# 02_H7_IO.net
KiCad netlist of a schematic drawn in Altium Designer
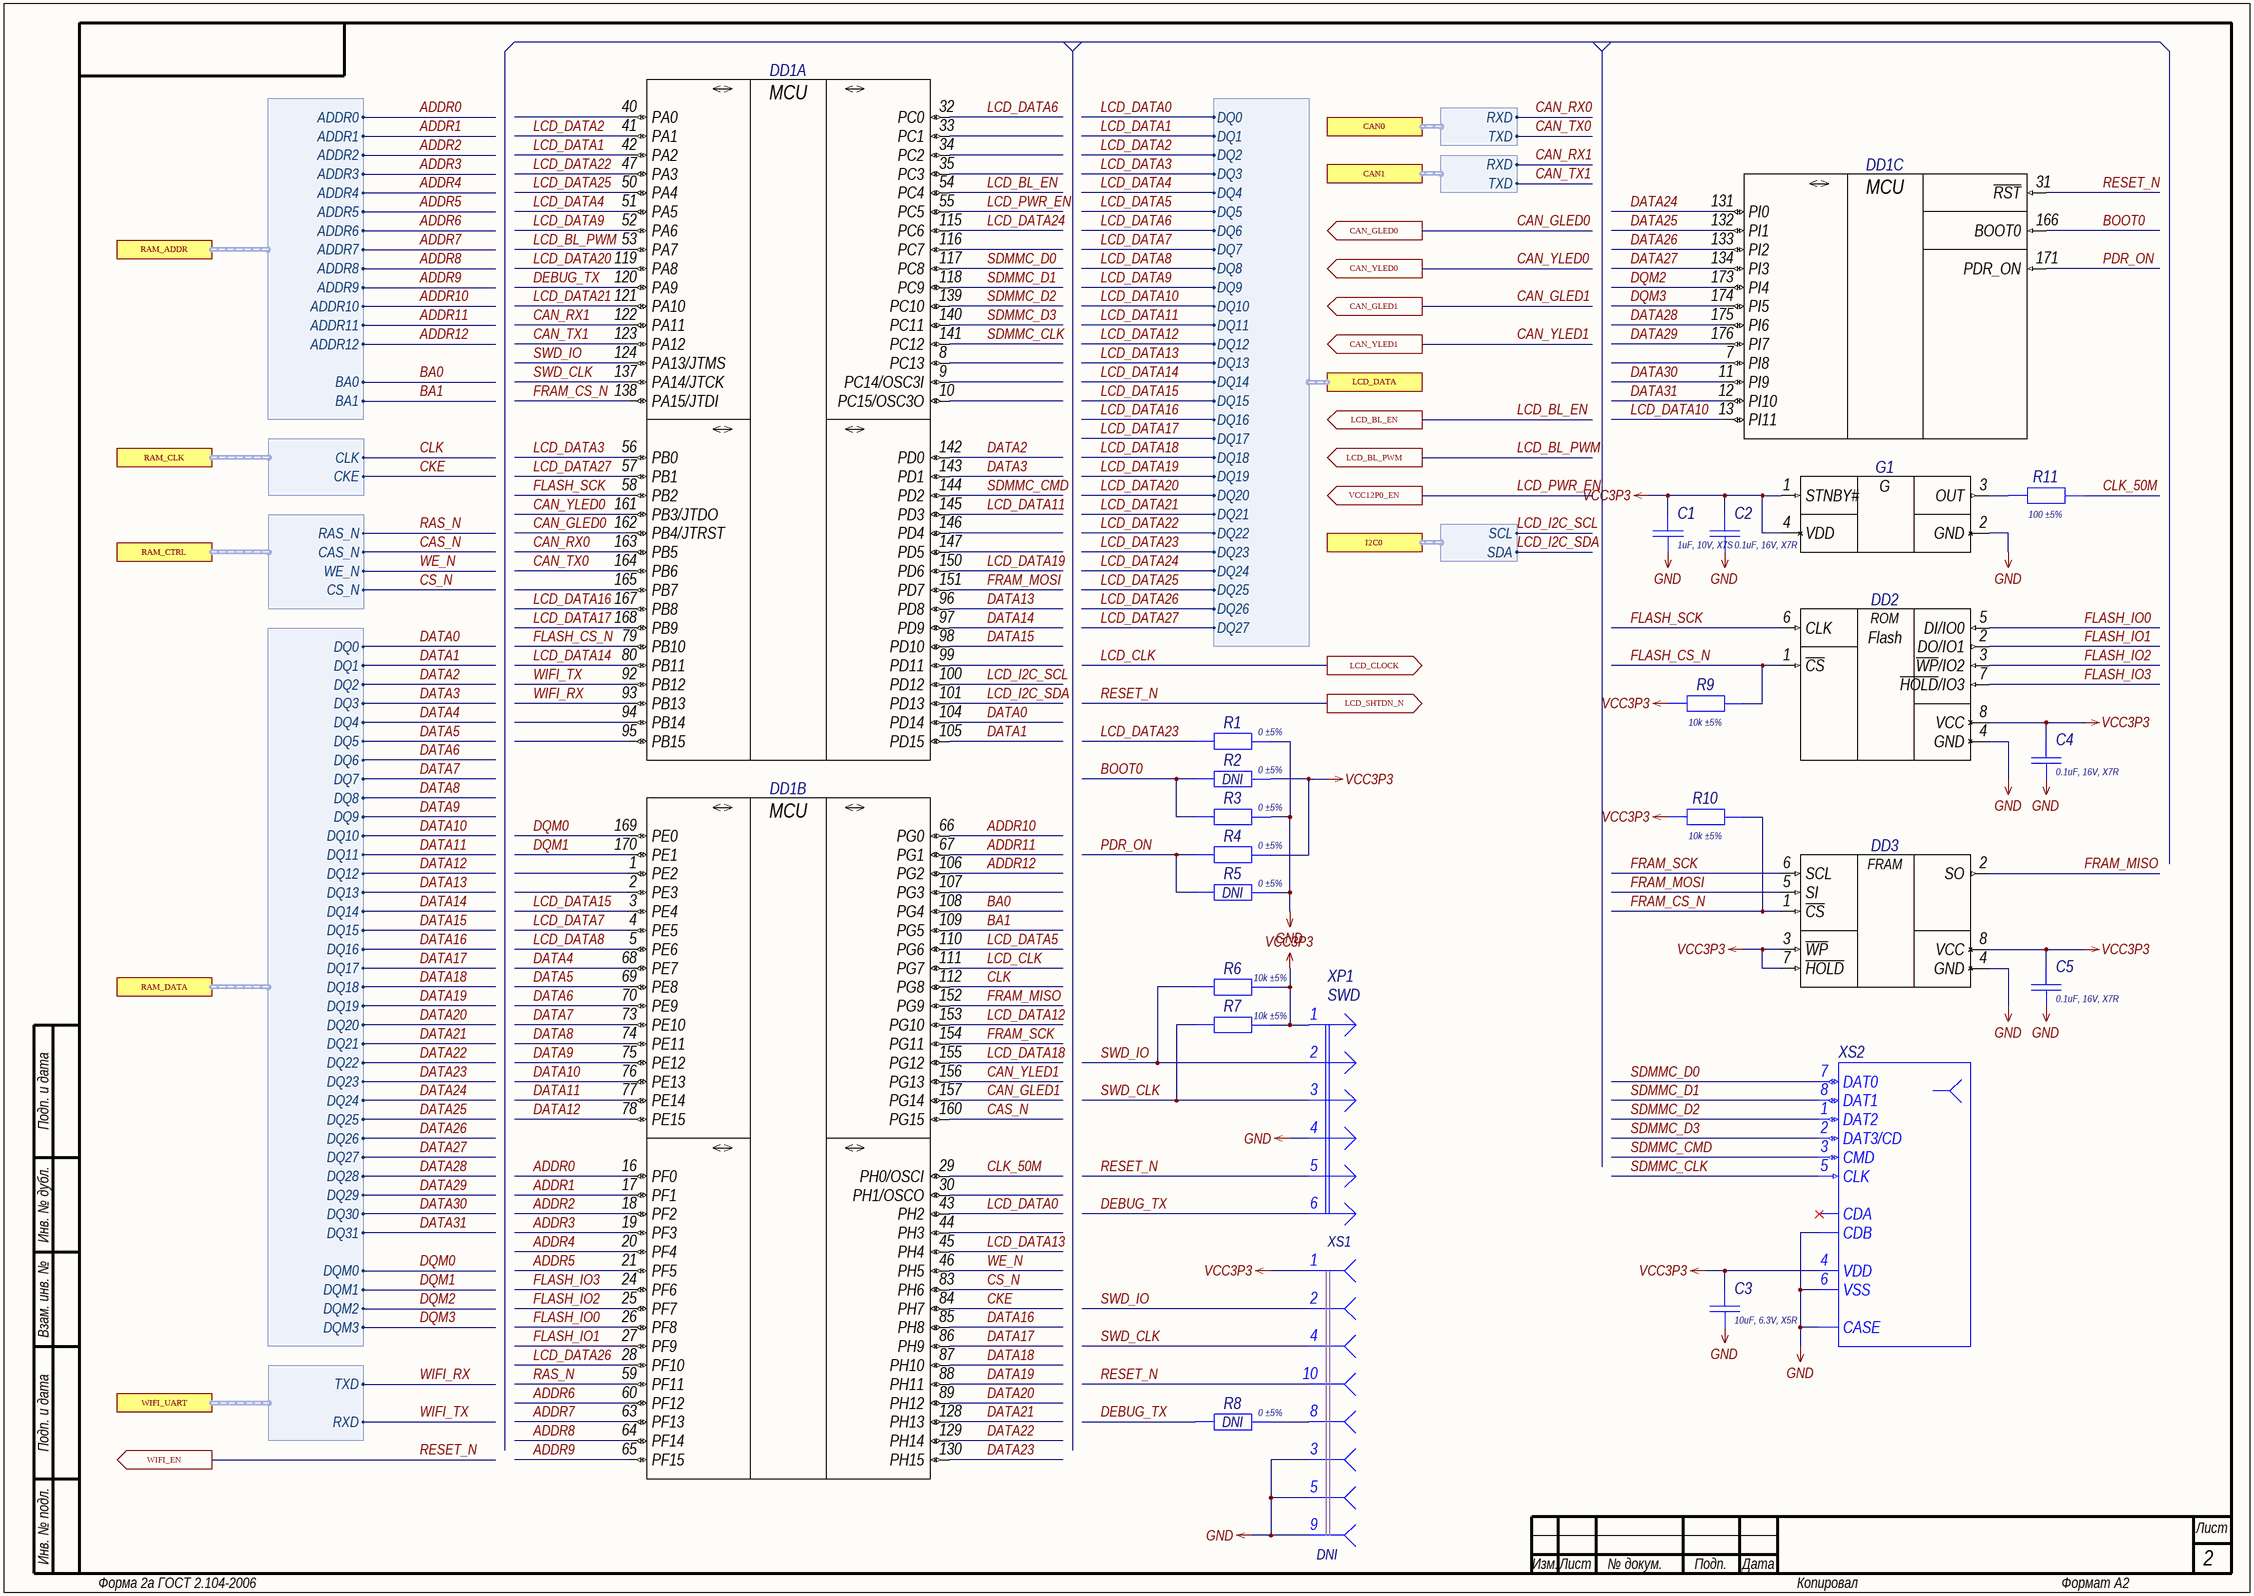
[diagram p0: 02_H7_IO.SchDoc]

(export (version "E")
  (design (tool "Eeschema 10.0.6"))
  (components
    (comp (ref "C1")
      (value "Capacitor")
      (footprint "C0402_L")
      (fields
        (field (name "SCHEMATIC VALUE") "1uF, 10V, X7S")
        (field (name "PART NUMBER") "GRM155C71A105KE11D")
        (field (name "VOLTAGE") "10V")
        (field (name "TOLERANCE") "±10%")
        (field (name "PUBLISHER") "Andrew Danich")
      )
      (libsource (lib "ADLib") (part "Capacitor"))
    )
    (comp (ref "C2")
      (value "Capacitor")
      (footprint "C0402_L")
      (fields
        (field (name "SCHEMATIC VALUE") "0.1uF, 16V, X7R")
        (field (name "PART NUMBER") "GCM155R71C104KA55D")
        (field (name "VOLTAGE") "16V")
        (field (name "TOLERANCE") "±10%")
        (field (name "PUBLISHER") "Andrew Danich")
      )
      (libsource (lib "ADLib") (part "Capacitor"))
    )
    (comp (ref "C3")
      (value "Capacitor")
      (footprint "C0402_L")
      (fields
        (field (name "SCHEMATIC VALUE") "10uF, 6.3V, X5R")
        (field (name "PART NUMBER") "GRM155R60J106ME15D")
        (field (name "VOLTAGE") "6.3V")
        (field (name "TOLERANCE") "±20%")
        (field (name "PUBLISHER") "Andrew Danich")
      )
      (libsource (lib "ADLib") (part "Capacitor"))
    )
    (comp (ref "C4")
      (value "Capacitor")
      (footprint "C0402_L")
      (fields
        (field (name "SCHEMATIC VALUE") "0.1uF, 16V, X7R")
        (field (name "PART NUMBER") "GCM155R71C104KA55D")
        (field (name "VOLTAGE") "16V")
        (field (name "TOLERANCE") "±10%")
        (field (name "PUBLISHER") "Andrew Danich")
      )
      (libsource (lib "ADLib") (part "Capacitor"))
    )
    (comp (ref "C5")
      (value "Capacitor")
      (footprint "C0402_L")
      (fields
        (field (name "SCHEMATIC VALUE") "0.1uF, 16V, X7R")
        (field (name "PART NUMBER") "GCM155R71C104KA55D")
        (field (name "VOLTAGE") "16V")
        (field (name "TOLERANCE") "±10%")
        (field (name "PUBLISHER") "Andrew Danich")
      )
      (libsource (lib "ADLib") (part "Capacitor"))
    )
    (comp (ref "DD1")
      (value "STM32H743IxT6-Series")
      (footprint "LQFP-176_050P2400X2400X160_N")
      (fields
        (field (name "PART NUMBER") "STM32H743IIT6")
        (field (name "MANUFACTURER") "STMicroelectronics")
        (field (name "PUBLISHER") "Andrew Danich")
      )
      (libsource (lib "ADLib") (part "STM32H743IxT6-Series"))
    )
    (comp (ref "DD2")
      (value "W25Q-Series")
      (footprint "SOIC-8_127P528X528X203_N")
      (fields
        (field (name "PART NUMBER") "W25Q128JVSIQ")
        (field (name "MANUFACTURER") "Winbond")
        (field (name "PUBLISHER") "Andrew Danich")
      )
      (libsource (lib "ADLib") (part "W25Q-Series"))
    )
    (comp (ref "DD3")
      (value "FM25CL64Bx-Series")
      (footprint "SOIC-8_127P490X391X155_N")
      (fields
        (field (name "PART NUMBER") "FM25CL64B-G")
        (field (name "MANUFACTURER") "Cypress Semiconductor")
        (field (name "PUBLISHER") "Andrew Danich")
      )
      (libsource (lib "ADLib") (part "FM25CL64Bx-Series"))
    )
    (comp (ref "G1")
      (value "DSC100X-Series")
      (footprint "CDFN-4_165P250X200X085_N")
      (fields
        (field (name "PART NUMBER") "DSC1001DI5-050.0000")
        (field (name "MANUFACTURER") "Microchip")
        (field (name "PUBLISHER") "Andrew Danich")
      )
      (libsource (lib "ADLib") (part "DSC100X-Series"))
    )
    (comp (ref "R1")
      (value "Resistor")
      (footprint "R0402_L")
      (fields
        (field (name "SCHEMATIC VALUE") "0 ±5%")
        (field (name "PART NUMBER") "RC0402JR-070RL")
        (field (name "TOLERANCE") "±5%")
        (field (name "MANUFACTURER") "Yageo")
        (field (name "PUBLISHER") "Andrew Danich")
      )
      (libsource (lib "ADLib") (part "Resistor"))
    )
    (comp (ref "R2")
      (value "Resistor")
      (footprint "R0402_L")
      (fields
        (field (name "SCHEMATIC VALUE") "0 ±5%")
        (field (name "PART NUMBER") "RC0402JR-070RL")
        (field (name "TOLERANCE") "±5%")
        (field (name "MANUFACTURER") "Yageo")
        (field (name "PUBLISHER") "Andrew Danich")
      )
      (libsource (lib "ADLib") (part "Resistor"))
    )
    (comp (ref "R3")
      (value "Resistor")
      (footprint "R0402_L")
      (fields
        (field (name "SCHEMATIC VALUE") "0 ±5%")
        (field (name "PART NUMBER") "RC0402JR-070RL")
        (field (name "TOLERANCE") "±5%")
        (field (name "MANUFACTURER") "Yageo")
        (field (name "PUBLISHER") "Andrew Danich")
      )
      (libsource (lib "ADLib") (part "Resistor"))
    )
    (comp (ref "R4")
      (value "Resistor")
      (footprint "R0402_L")
      (fields
        (field (name "SCHEMATIC VALUE") "0 ±5%")
        (field (name "PART NUMBER") "RC0402JR-070RL")
        (field (name "TOLERANCE") "±5%")
        (field (name "MANUFACTURER") "Yageo")
        (field (name "PUBLISHER") "Andrew Danich")
      )
      (libsource (lib "ADLib") (part "Resistor"))
    )
    (comp (ref "R5")
      (value "Resistor")
      (footprint "R0402_L")
      (fields
        (field (name "SCHEMATIC VALUE") "0 ±5%")
        (field (name "PART NUMBER") "RC0402JR-070RL")
        (field (name "TOLERANCE") "±5%")
        (field (name "MANUFACTURER") "Yageo")
        (field (name "PUBLISHER") "Andrew Danich")
      )
      (libsource (lib "ADLib") (part "Resistor"))
    )
    (comp (ref "R6")
      (value "Resistor")
      (footprint "R0402_L")
      (fields
        (field (name "SCHEMATIC VALUE") "10k ±5%")
        (field (name "PART NUMBER") "RC0402JR-0710KL")
        (field (name "TOLERANCE") "±5%")
        (field (name "MANUFACTURER") "Yageo")
        (field (name "PUBLISHER") "Andrew Danich")
      )
      (libsource (lib "ADLib") (part "Resistor"))
    )
    (comp (ref "R7")
      (value "Resistor")
      (footprint "R0402_L")
      (fields
        (field (name "SCHEMATIC VALUE") "10k ±5%")
        (field (name "PART NUMBER") "RC0402JR-0710KL")
        (field (name "TOLERANCE") "±5%")
        (field (name "MANUFACTURER") "Yageo")
        (field (name "PUBLISHER") "Andrew Danich")
      )
      (libsource (lib "ADLib") (part "Resistor"))
    )
    (comp (ref "R8")
      (value "Resistor")
      (footprint "R0402_L")
      (fields
        (field (name "SCHEMATIC VALUE") "0 ±5%")
        (field (name "PART NUMBER") "RC0402JR-070RL")
        (field (name "TOLERANCE") "±5%")
        (field (name "MANUFACTURER") "Yageo")
        (field (name "PUBLISHER") "Andrew Danich")
      )
      (libsource (lib "ADLib") (part "Resistor"))
    )
    (comp (ref "R9")
      (value "Resistor")
      (footprint "R0402_L")
      (fields
        (field (name "SCHEMATIC VALUE") "10k ±5%")
        (field (name "PART NUMBER") "RC0402JR-0710KL")
        (field (name "TOLERANCE") "±5%")
        (field (name "MANUFACTURER") "Yageo")
        (field (name "PUBLISHER") "Andrew Danich")
      )
      (libsource (lib "ADLib") (part "Resistor"))
    )
    (comp (ref "R10")
      (value "Resistor")
      (footprint "R0402_L")
      (fields
        (field (name "SCHEMATIC VALUE") "10k ±5%")
        (field (name "PART NUMBER") "RC0402JR-0710KL")
        (field (name "TOLERANCE") "±5%")
        (field (name "MANUFACTURER") "Yageo")
        (field (name "PUBLISHER") "Andrew Danich")
      )
      (libsource (lib "ADLib") (part "Resistor"))
    )
    (comp (ref "R11")
      (value "Resistor")
      (footprint "R0402_L")
      (fields
        (field (name "SCHEMATIC VALUE") "100 ±5%")
        (field (name "PART NUMBER") "RC0402JR-07100RL")
        (field (name "TOLERANCE") "±5%")
        (field (name "MANUFACTURER") "Yageo")
        (field (name "PUBLISHER") "Andrew Danich")
      )
      (libsource (lib "ADLib") (part "Resistor"))
    )
    (comp (ref "XP1")
      (value "SWD")
      (footprint "CWF-6R")
      (fields
        (field (name "PART NUMBER") "CWF-6R")
        (field (name "MANUFACTURER") "Ningbo Zhenqin Electronic")
        (field (name "PUBLISHER") "Andrew Danich")
      )
      (libsource (lib "ADLib") (part "Con-6-M"))
    )
    (comp (ref "XS1")
      (value "JTAG")
      (footprint "XF2M-1015-1A")
      (fields
        (field (name "PART NUMBER") "XF2M-1015-1A")
        (field (name "MANUFACTURER") "Omron Electronics")
        (field (name "PUBLISHER") "Viktor Klishin")
      )
      (libsource (lib "ADLib") (part "Con-10-F_S"))
    )
    (comp (ref "XS2")
      (value "DM3AT-SF-PEJM5")
      (footprint "DM3AT-SF-PEJM5")
      (fields (field (name "MANUFACTURER") "Hirose Connector") (field (name "PUBLISHER") "Andrew Danich"))
      (libsource (lib "ADLib") (part "DM3AT-SF-PEJM5"))
    )
  )
  (nets
    (net (code "9") (name "/ADDR0") (class "Default")
      (node (ref "DD1") (pin "16") (pinfunction "PF0_16") (pintype "bidirectional"))
    )
    (net (code "10") (name "/ADDR1") (class "Default")
      (node (ref "DD1") (pin "17") (pinfunction "PF1_17") (pintype "bidirectional"))
    )
    (net (code "11") (name "/ADDR2") (class "Default")
      (node (ref "DD1") (pin "18") (pinfunction "PF2_18") (pintype "bidirectional"))
    )
    (net (code "12") (name "/ADDR3") (class "Default")
      (node (ref "DD1") (pin "19") (pinfunction "PF3_19") (pintype "bidirectional"))
    )
    (net (code "13") (name "/ADDR4") (class "Default")
      (node (ref "DD1") (pin "20") (pinfunction "PF4_20") (pintype "bidirectional"))
    )
    (net (code "14") (name "/ADDR5") (class "Default")
      (node (ref "DD1") (pin "21") (pinfunction "PF5_21") (pintype "bidirectional"))
    )
    (net (code "15") (name "/ADDR6") (class "Default")
      (node (ref "DD1") (pin "60") (pinfunction "PF12_60") (pintype "bidirectional"))
    )
    (net (code "16") (name "/ADDR7") (class "Default")
      (node (ref "DD1") (pin "63") (pinfunction "PF13_63") (pintype "bidirectional"))
    )
    (net (code "17") (name "/ADDR8") (class "Default")
      (node (ref "DD1") (pin "64") (pinfunction "PF14_64") (pintype "bidirectional"))
    )
    (net (code "18") (name "/ADDR9") (class "Default")
      (node (ref "DD1") (pin "65") (pinfunction "PF15_65") (pintype "bidirectional"))
    )
    (net (code "19") (name "/ADDR10") (class "Default")
      (node (ref "DD1") (pin "66") (pinfunction "PG0_66") (pintype "bidirectional"))
    )
    (net (code "20") (name "/ADDR11") (class "Default")
      (node (ref "DD1") (pin "67") (pinfunction "PG1_67") (pintype "bidirectional"))
    )
    (net (code "21") (name "/ADDR12") (class "Default")
      (node (ref "DD1") (pin "106") (pinfunction "PG2_106") (pintype "bidirectional"))
    )
    (net (code "22") (name "/BA0") (class "Default")
      (node (ref "DD1") (pin "108") (pinfunction "PG4_108") (pintype "bidirectional"))
    )
    (net (code "23") (name "/BA1") (class "Default")
      (node (ref "DD1") (pin "109") (pinfunction "PG5_109") (pintype "bidirectional"))
    )
    (net (code "24") (name "/BOOT0") (class "Default")
      (node (ref "DD1") (pin "166") (pinfunction "BOOT0_166") (pintype "input"))
      (node (ref "R2") (pin "1") (pinfunction "1_1") (pintype "passive"))
      (node (ref "R3") (pin "1") (pinfunction "1_1") (pintype "passive"))
    )
    (net (code "25") (name "/CAN_GLED0") (class "Default")
      (node (ref "DD1") (pin "162") (pinfunction "PB4/JTRST_162") (pintype "bidirectional"))
    )
    (net (code "26") (name "/CAN_GLED1") (class "Default")
      (node (ref "DD1") (pin "157") (pinfunction "PG14_157") (pintype "bidirectional"))
    )
    (net (code "27") (name "/CAN_RX0") (class "Default")
      (node (ref "DD1") (pin "163") (pinfunction "PB5_163") (pintype "bidirectional"))
    )
    (net (code "28") (name "/CAN_RX1") (class "Default")
      (node (ref "DD1") (pin "122") (pinfunction "PA11_122") (pintype "bidirectional"))
    )
    (net (code "29") (name "/CAN_TX0") (class "Default")
      (node (ref "DD1") (pin "164") (pinfunction "PB6_164") (pintype "bidirectional"))
    )
    (net (code "30") (name "/CAN_TX1") (class "Default")
      (node (ref "DD1") (pin "123") (pinfunction "PA12_123") (pintype "bidirectional"))
    )
    (net (code "31") (name "/CAN_YLED0") (class "Default")
      (node (ref "DD1") (pin "161") (pinfunction "PB3/JTDO_161") (pintype "bidirectional"))
    )
    (net (code "32") (name "/CAN_YLED1") (class "Default")
      (node (ref "DD1") (pin "156") (pinfunction "PG13_156") (pintype "bidirectional"))
    )
    (net (code "33") (name "/CAS_N") (class "Default")
      (node (ref "DD1") (pin "160") (pinfunction "PG15_160") (pintype "bidirectional"))
    )
    (net (code "34") (name "/CKE") (class "Default")
      (node (ref "DD1") (pin "84") (pinfunction "PH7_84") (pintype "bidirectional"))
    )
    (net (code "35") (name "/CLK") (class "Default")
      (node (ref "DD1") (pin "112") (pinfunction "PG8_112") (pintype "bidirectional"))
    )
    (net (code "36") (name "/CLK_50M") (class "Default")
      (node (ref "DD1") (pin "29") (pinfunction "PH0/OSCI_29") (pintype "bidirectional"))
      (node (ref "R11") (pin "2") (pinfunction "2_2") (pintype "passive"))
    )
    (net (code "37") (name "/CS_N") (class "Default")
      (node (ref "DD1") (pin "83") (pinfunction "PH6_83") (pintype "bidirectional"))
    )
    (net (code "38") (name "/DATA0") (class "Default")
      (node (ref "DD1") (pin "104") (pinfunction "PD14_104") (pintype "bidirectional"))
    )
    (net (code "39") (name "/DATA1") (class "Default")
      (node (ref "DD1") (pin "105") (pinfunction "PD15_105") (pintype "bidirectional"))
    )
    (net (code "40") (name "/DATA2") (class "Default")
      (node (ref "DD1") (pin "142") (pinfunction "PD0_142") (pintype "bidirectional"))
    )
    (net (code "41") (name "/DATA3") (class "Default")
      (node (ref "DD1") (pin "143") (pinfunction "PD1_143") (pintype "bidirectional"))
    )
    (net (code "42") (name "/DATA4") (class "Default")
      (node (ref "DD1") (pin "68") (pinfunction "PE7_68") (pintype "bidirectional"))
    )
    (net (code "43") (name "/DATA5") (class "Default")
      (node (ref "DD1") (pin "69") (pinfunction "PE8_69") (pintype "bidirectional"))
    )
    (net (code "44") (name "/DATA6") (class "Default")
      (node (ref "DD1") (pin "70") (pinfunction "PE9_70") (pintype "bidirectional"))
    )
    (net (code "45") (name "/DATA7") (class "Default")
      (node (ref "DD1") (pin "73") (pinfunction "PE10_73") (pintype "bidirectional"))
    )
    (net (code "46") (name "/DATA8") (class "Default")
      (node (ref "DD1") (pin "74") (pinfunction "PE11_74") (pintype "bidirectional"))
    )
    (net (code "47") (name "/DATA9") (class "Default")
      (node (ref "DD1") (pin "75") (pinfunction "PE12_75") (pintype "bidirectional"))
    )
    (net (code "48") (name "/DATA10") (class "Default")
      (node (ref "DD1") (pin "76") (pinfunction "PE13_76") (pintype "bidirectional"))
    )
    (net (code "49") (name "/DATA11") (class "Default")
      (node (ref "DD1") (pin "77") (pinfunction "PE14_77") (pintype "bidirectional"))
    )
    (net (code "50") (name "/DATA12") (class "Default")
      (node (ref "DD1") (pin "78") (pinfunction "PE15_78") (pintype "bidirectional"))
    )
    (net (code "51") (name "/DATA13") (class "Default")
      (node (ref "DD1") (pin "96") (pinfunction "PD8_96") (pintype "bidirectional"))
    )
    (net (code "52") (name "/DATA14") (class "Default")
      (node (ref "DD1") (pin "97") (pinfunction "PD9_97") (pintype "bidirectional"))
    )
    (net (code "53") (name "/DATA15") (class "Default")
      (node (ref "DD1") (pin "98") (pinfunction "PD10_98") (pintype "bidirectional"))
    )
    (net (code "54") (name "/DATA16") (class "Default")
      (node (ref "DD1") (pin "85") (pinfunction "PH8_85") (pintype "bidirectional"))
    )
    (net (code "55") (name "/DATA17") (class "Default")
      (node (ref "DD1") (pin "86") (pinfunction "PH9_86") (pintype "bidirectional"))
    )
    (net (code "56") (name "/DATA18") (class "Default")
      (node (ref "DD1") (pin "87") (pinfunction "PH10_87") (pintype "bidirectional"))
    )
    (net (code "57") (name "/DATA19") (class "Default")
      (node (ref "DD1") (pin "88") (pinfunction "PH11_88") (pintype "bidirectional"))
    )
    (net (code "58") (name "/DATA20") (class "Default")
      (node (ref "DD1") (pin "89") (pinfunction "PH12_89") (pintype "bidirectional"))
    )
    (net (code "59") (name "/DATA21") (class "Default")
      (node (ref "DD1") (pin "128") (pinfunction "PH13_128") (pintype "bidirectional"))
    )
    (net (code "60") (name "/DATA22") (class "Default")
      (node (ref "DD1") (pin "129") (pinfunction "PH14_129") (pintype "bidirectional"))
    )
    (net (code "61") (name "/DATA23") (class "Default")
      (node (ref "DD1") (pin "130") (pinfunction "PH15_130") (pintype "bidirectional"))
    )
    (net (code "62") (name "/DATA24") (class "Default")
      (node (ref "DD1") (pin "131") (pinfunction "PI0_131") (pintype "bidirectional"))
    )
    (net (code "63") (name "/DATA25") (class "Default")
      (node (ref "DD1") (pin "132") (pinfunction "PI1_132") (pintype "bidirectional"))
    )
    (net (code "64") (name "/DATA26") (class "Default")
      (node (ref "DD1") (pin "133") (pinfunction "PI2_133") (pintype "bidirectional"))
    )
    (net (code "65") (name "/DATA27") (class "Default")
      (node (ref "DD1") (pin "134") (pinfunction "PI3_134") (pintype "bidirectional"))
    )
    (net (code "66") (name "/DATA28") (class "Default")
      (node (ref "DD1") (pin "175") (pinfunction "PI6_175") (pintype "bidirectional"))
    )
    (net (code "67") (name "/DATA29") (class "Default")
      (node (ref "DD1") (pin "176") (pinfunction "PI7_176") (pintype "bidirectional"))
    )
    (net (code "68") (name "/DATA30") (class "Default")
      (node (ref "DD1") (pin "11") (pinfunction "PI9_11") (pintype "bidirectional"))
    )
    (net (code "69") (name "/DATA31") (class "Default")
      (node (ref "DD1") (pin "12") (pinfunction "PI10_12") (pintype "bidirectional"))
    )
    (net (code "70") (name "/DEBUG_TX") (class "Default")
      (node (ref "DD1") (pin "120") (pinfunction "PA9_120") (pintype "bidirectional"))
      (node (ref "R8") (pin "1") (pinfunction "1_1") (pintype "passive"))
      (node (ref "XP1") (pin "6") (pintype "passive"))
    )
    (net (code "71") (name "/DQM0") (class "Default")
      (node (ref "DD1") (pin "169") (pinfunction "PE0_169") (pintype "bidirectional"))
    )
    (net (code "72") (name "/DQM1") (class "Default")
      (node (ref "DD1") (pin "170") (pinfunction "PE1_170") (pintype "bidirectional"))
    )
    (net (code "73") (name "/DQM2") (class "Default")
      (node (ref "DD1") (pin "173") (pinfunction "PI4_173") (pintype "bidirectional"))
    )
    (net (code "74") (name "/DQM3") (class "Default")
      (node (ref "DD1") (pin "174") (pinfunction "PI5_174") (pintype "bidirectional"))
    )
    (net (code "75") (name "/FLASH_CS_N") (class "Default")
      (node (ref "DD1") (pin "79") (pinfunction "PB10_79") (pintype "bidirectional"))
      (node (ref "DD2") (pin "1") (pinfunction "~{CS}_1") (pintype "input"))
      (node (ref "R9") (pin "1") (pinfunction "1_1") (pintype "passive"))
    )
    (net (code "76") (name "/FLASH_IO0") (class "Default")
      (node (ref "DD1") (pin "26") (pinfunction "PF8_26") (pintype "bidirectional"))
      (node (ref "DD2") (pin "5") (pinfunction "DI/IO0_5") (pintype "input"))
    )
    (net (code "77") (name "/FLASH_IO1") (class "Default")
      (node (ref "DD1") (pin "27") (pinfunction "PF9_27") (pintype "bidirectional"))
      (node (ref "DD2") (pin "2") (pinfunction "DO/IO1_2") (pintype "output"))
    )
    (net (code "78") (name "/FLASH_IO2") (class "Default")
      (node (ref "DD1") (pin "25") (pinfunction "PF7_25") (pintype "bidirectional"))
      (node (ref "DD2") (pin "3") (pinfunction "~{WP}/IO2_3") (pintype "input"))
    )
    (net (code "79") (name "/FLASH_IO3") (class "Default")
      (node (ref "DD1") (pin "24") (pinfunction "PF6_24") (pintype "bidirectional"))
      (node (ref "DD2") (pin "7") (pinfunction "~{HOLD}/IO3_7") (pintype "input"))
    )
    (net (code "80") (name "/FLASH_SCK") (class "Default")
      (node (ref "DD1") (pin "58") (pinfunction "PB2_58") (pintype "bidirectional"))
      (node (ref "DD2") (pin "6") (pinfunction "CLK_6") (pintype "input"))
    )
    (net (code "81") (name "/FRAM_CS_N") (class "Default")
      (node (ref "DD1") (pin "138") (pinfunction "PA15/JTDI_138") (pintype "bidirectional"))
      (node (ref "DD3") (pin "1") (pinfunction "~{CS}_1") (pintype "input"))
      (node (ref "R10") (pin "1") (pinfunction "1_1") (pintype "passive"))
    )
    (net (code "82") (name "/FRAM_MISO") (class "Default")
      (node (ref "DD1") (pin "152") (pinfunction "PG9_152") (pintype "bidirectional"))
      (node (ref "DD3") (pin "2") (pinfunction "SO_2") (pintype "output"))
    )
    (net (code "83") (name "/FRAM_MOSI") (class "Default")
      (node (ref "DD1") (pin "151") (pinfunction "PD7_151") (pintype "bidirectional"))
      (node (ref "DD3") (pin "5") (pinfunction "SI_5") (pintype "input"))
    )
    (net (code "84") (name "/FRAM_SCK") (class "Default")
      (node (ref "DD1") (pin "154") (pinfunction "PG11_154") (pintype "bidirectional"))
      (node (ref "DD3") (pin "6") (pinfunction "SCL_6") (pintype "input"))
    )
    (net (code "85") (name "/LCD_BL_EN") (class "Default")
      (node (ref "DD1") (pin "54") (pinfunction "PC4_54") (pintype "bidirectional"))
    )
    (net (code "86") (name "/LCD_BL_PWM") (class "Default")
      (node (ref "DD1") (pin "53") (pinfunction "PA7_53") (pintype "bidirectional"))
    )
    (net (code "87") (name "/LCD_CLK") (class "Default")
      (node (ref "DD1") (pin "111") (pinfunction "PG7_111") (pintype "bidirectional"))
    )
    (net (code "88") (name "/LCD_DATA0") (class "Default")
      (node (ref "DD1") (pin "43") (pinfunction "PH2_43") (pintype "bidirectional"))
    )
    (net (code "89") (name "/LCD_DATA1") (class "Default")
      (node (ref "DD1") (pin "42") (pinfunction "PA2_42") (pintype "bidirectional"))
    )
    (net (code "90") (name "/LCD_DATA2") (class "Default")
      (node (ref "DD1") (pin "41") (pinfunction "PA1_41") (pintype "bidirectional"))
    )
    (net (code "91") (name "/LCD_DATA3") (class "Default")
      (node (ref "DD1") (pin "56") (pinfunction "PB0_56") (pintype "bidirectional"))
    )
    (net (code "92") (name "/LCD_DATA4") (class "Default")
      (node (ref "DD1") (pin "51") (pinfunction "PA5_51") (pintype "bidirectional"))
    )
    (net (code "93") (name "/LCD_DATA5") (class "Default")
      (node (ref "DD1") (pin "110") (pinfunction "PG6_110") (pintype "bidirectional"))
    )
    (net (code "94") (name "/LCD_DATA6") (class "Default")
      (node (ref "DD1") (pin "32") (pinfunction "PC0_32") (pintype "bidirectional"))
    )
    (net (code "95") (name "/LCD_DATA7") (class "Default")
      (node (ref "DD1") (pin "4") (pinfunction "PE5_4") (pintype "bidirectional"))
    )
    (net (code "96") (name "/LCD_DATA8") (class "Default")
      (node (ref "DD1") (pin "5") (pinfunction "PE6_5") (pintype "bidirectional"))
    )
    (net (code "97") (name "/LCD_DATA9") (class "Default")
      (node (ref "DD1") (pin "52") (pinfunction "PA6_52") (pintype "bidirectional"))
    )
    (net (code "98") (name "/LCD_DATA10") (class "Default")
      (node (ref "DD1") (pin "13") (pinfunction "PI11_13") (pintype "bidirectional"))
    )
    (net (code "99") (name "/LCD_DATA11") (class "Default")
      (node (ref "DD1") (pin "145") (pinfunction "PD3_145") (pintype "bidirectional"))
    )
    (net (code "100") (name "/LCD_DATA12") (class "Default")
      (node (ref "DD1") (pin "153") (pinfunction "PG10_153") (pintype "bidirectional"))
    )
    (net (code "101") (name "/LCD_DATA13") (class "Default")
      (node (ref "DD1") (pin "45") (pinfunction "PH4_45") (pintype "bidirectional"))
    )
    (net (code "102") (name "/LCD_DATA14") (class "Default")
      (node (ref "DD1") (pin "80") (pinfunction "PB11_80") (pintype "bidirectional"))
    )
    (net (code "103") (name "/LCD_DATA15") (class "Default")
      (node (ref "DD1") (pin "3") (pinfunction "PE4_3") (pintype "bidirectional"))
    )
    (net (code "104") (name "/LCD_DATA16") (class "Default")
      (node (ref "DD1") (pin "167") (pinfunction "PB8_167") (pintype "bidirectional"))
    )
    (net (code "105") (name "/LCD_DATA17") (class "Default")
      (node (ref "DD1") (pin "168") (pinfunction "PB9_168") (pintype "bidirectional"))
    )
    (net (code "106") (name "/LCD_DATA18") (class "Default")
      (node (ref "DD1") (pin "155") (pinfunction "PG12_155") (pintype "bidirectional"))
    )
    (net (code "107") (name "/LCD_DATA19") (class "Default")
      (node (ref "DD1") (pin "150") (pinfunction "PD6_150") (pintype "bidirectional"))
    )
    (net (code "108") (name "/LCD_DATA20") (class "Default")
      (node (ref "DD1") (pin "119") (pinfunction "PA8_119") (pintype "bidirectional"))
    )
    (net (code "109") (name "/LCD_DATA21") (class "Default")
      (node (ref "DD1") (pin "121") (pinfunction "PA10_121") (pintype "bidirectional"))
    )
    (net (code "110") (name "/LCD_DATA22") (class "Default")
      (node (ref "DD1") (pin "47") (pinfunction "PA3_47") (pintype "bidirectional"))
    )
    (net (code "111") (name "/LCD_DATA23") (class "Default")
      (node (ref "R1") (pin "1") (pinfunction "1_1") (pintype "passive"))
    )
    (net (code "112") (name "/LCD_DATA24") (class "Default")
      (node (ref "DD1") (pin "115") (pinfunction "PC6_115") (pintype "bidirectional"))
    )
    (net (code "113") (name "/LCD_DATA25") (class "Default")
      (node (ref "DD1") (pin "50") (pinfunction "PA4_50") (pintype "bidirectional"))
    )
    (net (code "114") (name "/LCD_DATA26") (class "Default")
      (node (ref "DD1") (pin "28") (pinfunction "PF10_28") (pintype "bidirectional"))
    )
    (net (code "115") (name "/LCD_DATA27") (class "Default")
      (node (ref "DD1") (pin "57") (pinfunction "PB1_57") (pintype "bidirectional"))
    )
    (net (code "116") (name "/LCD_I2C_SCL") (class "Default")
      (node (ref "DD1") (pin "100") (pinfunction "PD12_100") (pintype "bidirectional"))
    )
    (net (code "117") (name "/LCD_I2C_SDA") (class "Default")
      (node (ref "DD1") (pin "101") (pinfunction "PD13_101") (pintype "bidirectional"))
    )
    (net (code "118") (name "/LCD_PWR_EN") (class "Default")
      (node (ref "DD1") (pin "55") (pinfunction "PC5_55") (pintype "bidirectional"))
    )
    (net (code "119") (name "/PDR_ON") (class "Default")
      (node (ref "DD1") (pin "171") (pinfunction "PDR_ON_171") (pintype "input"))
      (node (ref "R4") (pin "1") (pinfunction "1_1") (pintype "passive"))
      (node (ref "R5") (pin "1") (pinfunction "1_1") (pintype "passive"))
    )
    (net (code "120") (name "/RAS_N") (class "Default")
      (node (ref "DD1") (pin "59") (pinfunction "PF11_59") (pintype "bidirectional"))
    )
    (net (code "121") (name "/RESET_N") (class "Default")
      (node (ref "DD1") (pin "31") (pinfunction "~{RST}_31") (pintype "input"))
      (node (ref "XP1") (pin "5") (pintype "passive"))
      (node (ref "XS1") (pin "10") (pintype "passive"))
    )
    (net (code "122") (name "/SDMMC_CLK") (class "Default")
      (node (ref "DD1") (pin "141") (pinfunction "PC12_141") (pintype "bidirectional"))
      (node (ref "XS2") (pin "5") (pinfunction "CLK_5") (pintype "input"))
    )
    (net (code "123") (name "/SDMMC_CMD") (class "Default")
      (node (ref "DD1") (pin "144") (pinfunction "PD2_144") (pintype "bidirectional"))
      (node (ref "XS2") (pin "3") (pinfunction "CMD_3") (pintype "bidirectional"))
    )
    (net (code "124") (name "/SDMMC_D0") (class "Default")
      (node (ref "DD1") (pin "117") (pinfunction "PC8_117") (pintype "bidirectional"))
      (node (ref "XS2") (pin "7") (pinfunction "DAT0_7") (pintype "bidirectional"))
    )
    (net (code "125") (name "/SDMMC_D1") (class "Default")
      (node (ref "DD1") (pin "118") (pinfunction "PC9_118") (pintype "bidirectional"))
      (node (ref "XS2") (pin "8") (pinfunction "DAT1_8") (pintype "bidirectional"))
    )
    (net (code "126") (name "/SDMMC_D2") (class "Default")
      (node (ref "DD1") (pin "139") (pinfunction "PC10_139") (pintype "bidirectional"))
      (node (ref "XS2") (pin "1") (pinfunction "DAT2_1") (pintype "bidirectional"))
    )
    (net (code "127") (name "/SDMMC_D3") (class "Default")
      (node (ref "DD1") (pin "140") (pinfunction "PC11_140") (pintype "bidirectional"))
      (node (ref "XS2") (pin "2") (pinfunction "DAT3/CD_2") (pintype "bidirectional"))
    )
    (net (code "128") (name "/SWD_CLK") (class "Default")
      (node (ref "DD1") (pin "137") (pinfunction "PA14/JTCK_137") (pintype "bidirectional"))
      (node (ref "R7") (pin "2") (pinfunction "2_2") (pintype "passive"))
      (node (ref "XP1") (pin "3") (pintype "passive"))
      (node (ref "XS1") (pin "4") (pintype "passive"))
    )
    (net (code "129") (name "/SWD_IO") (class "Default")
      (node (ref "DD1") (pin "124") (pinfunction "PA13/JTMS_124") (pintype "bidirectional"))
      (node (ref "R6") (pin "2") (pinfunction "2_2") (pintype "passive"))
      (node (ref "XP1") (pin "2") (pintype "passive"))
      (node (ref "XS1") (pin "2") (pintype "passive"))
    )
    (net (code "130") (name "/WE_N") (class "Default")
      (node (ref "DD1") (pin "46") (pinfunction "PH5_46") (pintype "bidirectional"))
    )
    (net (code "131") (name "/WIFI_RX") (class "Default")
      (node (ref "DD1") (pin "93") (pinfunction "PB13_93") (pintype "bidirectional"))
    )
    (net (code "132") (name "/WIFI_TX") (class "Default")
      (node (ref "DD1") (pin "92") (pinfunction "PB12_92") (pintype "bidirectional"))
    )
    (net (code "141") (name "GND") (class "Default")
      (node (ref "C1") (pin "1") (pinfunction "1_1") (pintype "passive"))
      (node (ref "C2") (pin "1") (pinfunction "1_1") (pintype "passive"))
      (node (ref "C3") (pin "1") (pinfunction "1_1") (pintype "passive"))
      (node (ref "C4") (pin "1") (pinfunction "1_1") (pintype "passive"))
      (node (ref "C5") (pin "1") (pinfunction "1_1") (pintype "passive"))
      (node (ref "DD2") (pin "4") (pinfunction "GND_4") (pintype "power_in"))
      (node (ref "DD3") (pin "4") (pinfunction "GND_4") (pintype "power_in"))
      (node (ref "G1") (pin "2") (pinfunction "GND_2") (pintype "power_in"))
      (node (ref "R1") (pin "2") (pinfunction "2_2") (pintype "passive"))
      (node (ref "R3") (pin "2") (pinfunction "2_2") (pintype "passive"))
      (node (ref "R5") (pin "2") (pinfunction "2_2") (pintype "passive"))
      (node (ref "XP1") (pin "4") (pintype "passive"))
      (node (ref "XS1") (pin "3") (pintype "passive"))
      (node (ref "XS1") (pin "5") (pintype "passive"))
      (node (ref "XS1") (pin "9") (pintype "passive"))
      (node (ref "XS2") (pin "6") (pinfunction "VSS_6") (pintype "power_in"))
      (node (ref "XS2") (pin "CASE") (pinfunction "CASE_CASE") (pintype "passive"))
      (node (ref "XS2") (pin "CDB") (pinfunction "CDB_CDB") (pintype "passive"))
    )
    (net (code "142") (name "Net-(G1-OUT)") (class "Default")
      (node (ref "G1") (pin "3") (pinfunction "OUT_3") (pintype "output"))
      (node (ref "R11") (pin "1") (pinfunction "1_1") (pintype "passive"))
    )
    (net (code "143") (name "Net-(R8-Pad2)") (class "Default")
      (node (ref "R8") (pin "2") (pinfunction "2_2") (pintype "passive"))
      (node (ref "XS1") (pin "8") (pintype "passive"))
    )
    (net (code "144") (name "VCC3P3") (class "Default")
      (node (ref "C1") (pin "2") (pinfunction "2_2") (pintype "passive"))
      (node (ref "C2") (pin "2") (pinfunction "2_2") (pintype "passive"))
      (node (ref "C3") (pin "2") (pinfunction "2_2") (pintype "passive"))
      (node (ref "C4") (pin "2") (pinfunction "2_2") (pintype "passive"))
      (node (ref "C5") (pin "2") (pinfunction "2_2") (pintype "passive"))
      (node (ref "DD2") (pin "8") (pinfunction "VCC_8") (pintype "power_in"))
      (node (ref "DD3") (pin "3") (pinfunction "~{WP}_3") (pintype "input"))
      (node (ref "DD3") (pin "7") (pinfunction "~{HOLD}_7") (pintype "input"))
      (node (ref "DD3") (pin "8") (pinfunction "VCC_8") (pintype "power_in"))
      (node (ref "G1") (pin "1") (pinfunction "STNBY#_1") (pintype "input"))
      (node (ref "G1") (pin "4") (pinfunction "VDD_4") (pintype "power_in"))
      (node (ref "R10") (pin "2") (pinfunction "2_2") (pintype "passive"))
      (node (ref "R2") (pin "2") (pinfunction "2_2") (pintype "passive"))
      (node (ref "R4") (pin "2") (pinfunction "2_2") (pintype "passive"))
      (node (ref "R6") (pin "1") (pinfunction "1_1") (pintype "passive"))
      (node (ref "R7") (pin "1") (pinfunction "1_1") (pintype "passive"))
      (node (ref "R9") (pin "2") (pinfunction "2_2") (pintype "passive"))
      (node (ref "XP1") (pin "1") (pintype "passive"))
      (node (ref "XS1") (pin "1") (pintype "passive"))
      (node (ref "XS2") (pin "4") (pinfunction "VDD_4") (pintype "power_in"))
    )
    (net (code "145") (name "unconnected-(DD1A-PA0-Pad40)") (class "Default")
      (node (ref "DD1") (pin "40") (pinfunction "PA0_40") (pintype "bidirectional"))
    )
    (net (code "146") (name "unconnected-(DD1A-PB7-Pad165)") (class "Default")
      (node (ref "DD1") (pin "165") (pinfunction "PB7_165") (pintype "bidirectional"))
    )
    (net (code "147") (name "unconnected-(DD1A-PB14-Pad94)") (class "Default")
      (node (ref "DD1") (pin "94") (pinfunction "PB14_94") (pintype "bidirectional"))
    )
    (net (code "148") (name "unconnected-(DD1A-PB15-Pad95)") (class "Default")
      (node (ref "DD1") (pin "95") (pinfunction "PB15_95") (pintype "bidirectional"))
    )
    (net (code "149") (name "unconnected-(DD1A-PC1-Pad33)") (class "Default")
      (node (ref "DD1") (pin "33") (pinfunction "PC1_33") (pintype "bidirectional"))
    )
    (net (code "150") (name "unconnected-(DD1A-PC2-Pad34)") (class "Default")
      (node (ref "DD1") (pin "34") (pinfunction "PC2_34") (pintype "bidirectional"))
    )
    (net (code "151") (name "unconnected-(DD1A-PC3-Pad35)") (class "Default")
      (node (ref "DD1") (pin "35") (pinfunction "PC3_35") (pintype "bidirectional"))
    )
    (net (code "152") (name "unconnected-(DD1A-PC7-Pad116)") (class "Default")
      (node (ref "DD1") (pin "116") (pinfunction "PC7_116") (pintype "bidirectional"))
    )
    (net (code "153") (name "unconnected-(DD1A-PC13-Pad8)") (class "Default")
      (node (ref "DD1") (pin "8") (pinfunction "PC13_8") (pintype "bidirectional"))
    )
    (net (code "154") (name "unconnected-(DD1A-PC14{slash}OSC3I-Pad9)") (class "Default")
      (node (ref "DD1") (pin "9") (pinfunction "PC14/OSC3I_9") (pintype "bidirectional"))
    )
    (net (code "155") (name "unconnected-(DD1A-PC15{slash}OSC3O-Pad10)") (class "Default")
      (node (ref "DD1") (pin "10") (pinfunction "PC15/OSC3O_10") (pintype "bidirectional"))
    )
    (net (code "156") (name "unconnected-(DD1A-PD4-Pad146)") (class "Default")
      (node (ref "DD1") (pin "146") (pinfunction "PD4_146") (pintype "bidirectional"))
    )
    (net (code "157") (name "unconnected-(DD1A-PD5-Pad147)") (class "Default")
      (node (ref "DD1") (pin "147") (pinfunction "PD5_147") (pintype "bidirectional"))
    )
    (net (code "158") (name "unconnected-(DD1A-PD11-Pad99)") (class "Default")
      (node (ref "DD1") (pin "99") (pinfunction "PD11_99") (pintype "bidirectional"))
    )
    (net (code "159") (name "unconnected-(DD1B-PE2-Pad1)") (class "Default")
      (node (ref "DD1") (pin "1") (pinfunction "PE2_1") (pintype "bidirectional"))
    )
    (net (code "160") (name "unconnected-(DD1B-PE3-Pad2)") (class "Default")
      (node (ref "DD1") (pin "2") (pinfunction "PE3_2") (pintype "bidirectional"))
    )
    (net (code "161") (name "unconnected-(DD1B-PG3-Pad107)") (class "Default")
      (node (ref "DD1") (pin "107") (pinfunction "PG3_107") (pintype "bidirectional"))
    )
    (net (code "162") (name "unconnected-(DD1B-PH1{slash}OSCO-Pad30)") (class "Default")
      (node (ref "DD1") (pin "30") (pinfunction "PH1/OSCO_30") (pintype "bidirectional"))
    )
    (net (code "163") (name "unconnected-(DD1B-PH3-Pad44)") (class "Default")
      (node (ref "DD1") (pin "44") (pinfunction "PH3_44") (pintype "bidirectional"))
    )
    (net (code "164") (name "unconnected-(DD1C-PI8-Pad7)") (class "Default")
      (node (ref "DD1") (pin "7") (pinfunction "PI8_7") (pintype "bidirectional"))
    )
    (net (code "165") (name "unconnected-(XS2-PadCDA)") (class "Default")
      (node (ref "XS2") (pin "CDA") (pinfunction "CDA_CDA") (pintype "passive+no_connect"))
    )
  )
)
